# canbus.net
KiCad netlist of a schematic drawn in Altium Designer
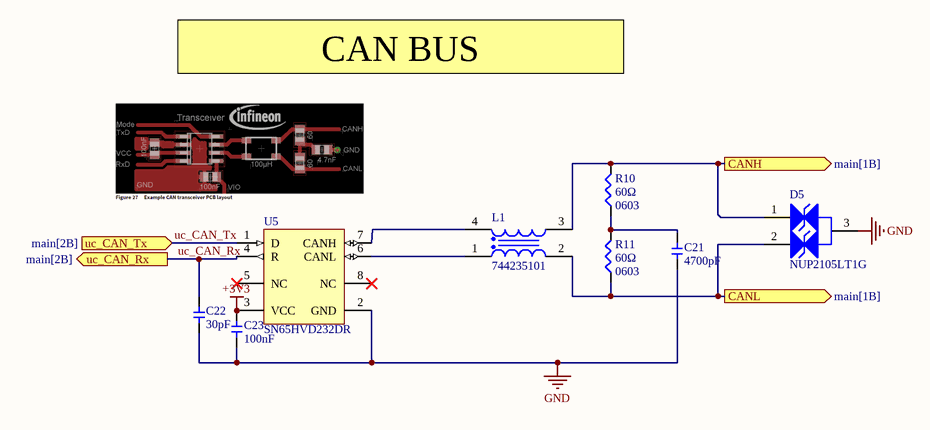
[diagram p0: canbus.SchDoc]

(export (version "E")
  (design (tool "Eeschema 10.0.6"))
  (components
    (comp (ref "C21")
      (value "4700pF")
      (footprint "0603_cap")
      (fields (field (name "Comment") "0603_4700pF"))
      (libsource (lib "generic") (part "0603_4700pF"))
    )
    (comp (ref "C22")
      (value "30pF")
      (footprint "0603_cap")
      (fields (field (name "Comment") "0603_30pF"))
      (libsource (lib "generic") (part "0603_30pF"))
    )
    (comp (ref "C23")
      (value "100nF")
      (footprint "0603_cap")
      (fields (field (name "Comment") "0603_100nF"))
      (libsource (lib "generic") (part "0603_100nF"))
    )
    (comp (ref "D5")
      (value "NUP2105LT1G")
      (footprint "ONSC-SOT-23-3-318-08_V")
      (description "Dual Line CAN Bus Protector, 3-Pin SOT-23, Pb-Free, Tape and Reel")
      (fields (field (name "MANUFACTURER") "On Semiconductor"))
      (libsource (lib "Altium Content Vault") (part "ONSC-NUP21X5X-SOT-23-3-318-08"))
    )
    (comp (ref "L1")
      (value "744235101")
      (footprint "WE-CNSW_1812")
      (description "CMC 100UH 150MA 2LN 8 KOHM SMD")
      (libsource (lib "Altium Content Vault") (part "WE-CNSW"))
    )
    (comp (ref "R10")
      (value "60Ω")
      (footprint "0603-smd")
      (fields (field (name "POWER") "W") (field (name "PACKAGE") "0603") (field (name "Comment") "0603_60R"))
      (libsource (lib "generic") (part "0603_60R"))
    )
    (comp (ref "R11")
      (value "60Ω")
      (footprint "0603-smd")
      (fields (field (name "POWER") "W") (field (name "PACKAGE") "0603") (field (name "Comment") "0603_60R"))
      (libsource (lib "generic") (part "0603_60R"))
    )
    (comp (ref "U5")
      (value "SN65HVD232DR")
      (footprint "D0008A_M")
      (description "3.3 V Can Transceiver, 17 mA, -40 to 85 degC, 8-pin SOIC (D), Green (RoHS & no Sb/Br)")
      (fields (field (name "MANUFACTURER") "Texas Instruments"))
      (libsource (lib "Altium Content Vault") (part "TI-SN65HVD232-SOIC_D-8"))
    )
  )
  (nets
    (net (code "1") (name "+3V3") (class "Default")
      (node (ref "C23") (pin "2") (pinfunction "2_2") (pintype "passive"))
      (node (ref "U5") (pin "3") (pinfunction "VCC_3") (pintype "power_in"))
    )
    (net (code "2") (name "/CANH") (class "Default")
      (node (ref "D5") (pin "1") (pinfunction "K_1") (pintype "passive"))
      (node (ref "L1") (pin "3") (pinfunction "3_3") (pintype "passive"))
      (node (ref "R10") (pin "2") (pinfunction "2_2") (pintype "passive"))
    )
    (net (code "3") (name "/CANL") (class "Default")
      (node (ref "D5") (pin "2") (pinfunction "K_2") (pintype "passive"))
      (node (ref "L1") (pin "2") (pinfunction "2_2") (pintype "passive"))
      (node (ref "R11") (pin "1") (pinfunction "1_1") (pintype "passive"))
    )
    (net (code "4") (name "/uc_CAN_Rx") (class "Default")
      (node (ref "C22") (pin "2") (pinfunction "2_2") (pintype "passive"))
      (node (ref "U5") (pin "4") (pinfunction "R_4") (pintype "output"))
    )
    (net (code "5") (name "/uc_CAN_Tx") (class "Default")
      (node (ref "U5") (pin "1") (pinfunction "D_1") (pintype "input"))
    )
    (net (code "6") (name "GND") (class "Default")
      (node (ref "C21") (pin "1") (pinfunction "1_1") (pintype "passive"))
      (node (ref "C22") (pin "1") (pinfunction "1_1") (pintype "passive"))
      (node (ref "C23") (pin "1") (pinfunction "1_1") (pintype "passive"))
      (node (ref "D5") (pin "3") (pinfunction "K_3") (pintype "passive"))
      (node (ref "U5") (pin "2") (pinfunction "GND_2") (pintype "power_in"))
    )
    (net (code "7") (name "Net-(C21-Pad2)") (class "Default")
      (node (ref "C21") (pin "2") (pinfunction "2_2") (pintype "passive"))
      (node (ref "R10") (pin "1") (pinfunction "1_1") (pintype "passive"))
      (node (ref "R11") (pin "2") (pinfunction "2_2") (pintype "passive"))
    )
    (net (code "8") (name "Net-(U5-CANH)") (class "Default")
      (node (ref "L1") (pin "4") (pinfunction "4_4") (pintype "passive"))
      (node (ref "U5") (pin "7") (pinfunction "CANH_7") (pintype "bidirectional"))
    )
    (net (code "9") (name "Net-(U5-CANL)") (class "Default")
      (node (ref "L1") (pin "1") (pinfunction "1_1") (pintype "passive"))
      (node (ref "U5") (pin "6") (pinfunction "CANL_6") (pintype "bidirectional"))
    )
    (net (code "10") (name "unconnected-(U5-NC-Pad5)") (class "Default")
      (node (ref "U5") (pin "5") (pinfunction "NC_5") (pintype "passive+no_connect"))
    )
    (net (code "11") (name "unconnected-(U5-NC-Pad8)") (class "Default")
      (node (ref "U5") (pin "8") (pinfunction "NC_8") (pintype "passive+no_connect"))
    )
  )
)
